# crankshaft_angle.net
KiCad netlist of a schematic drawn in EAGLE
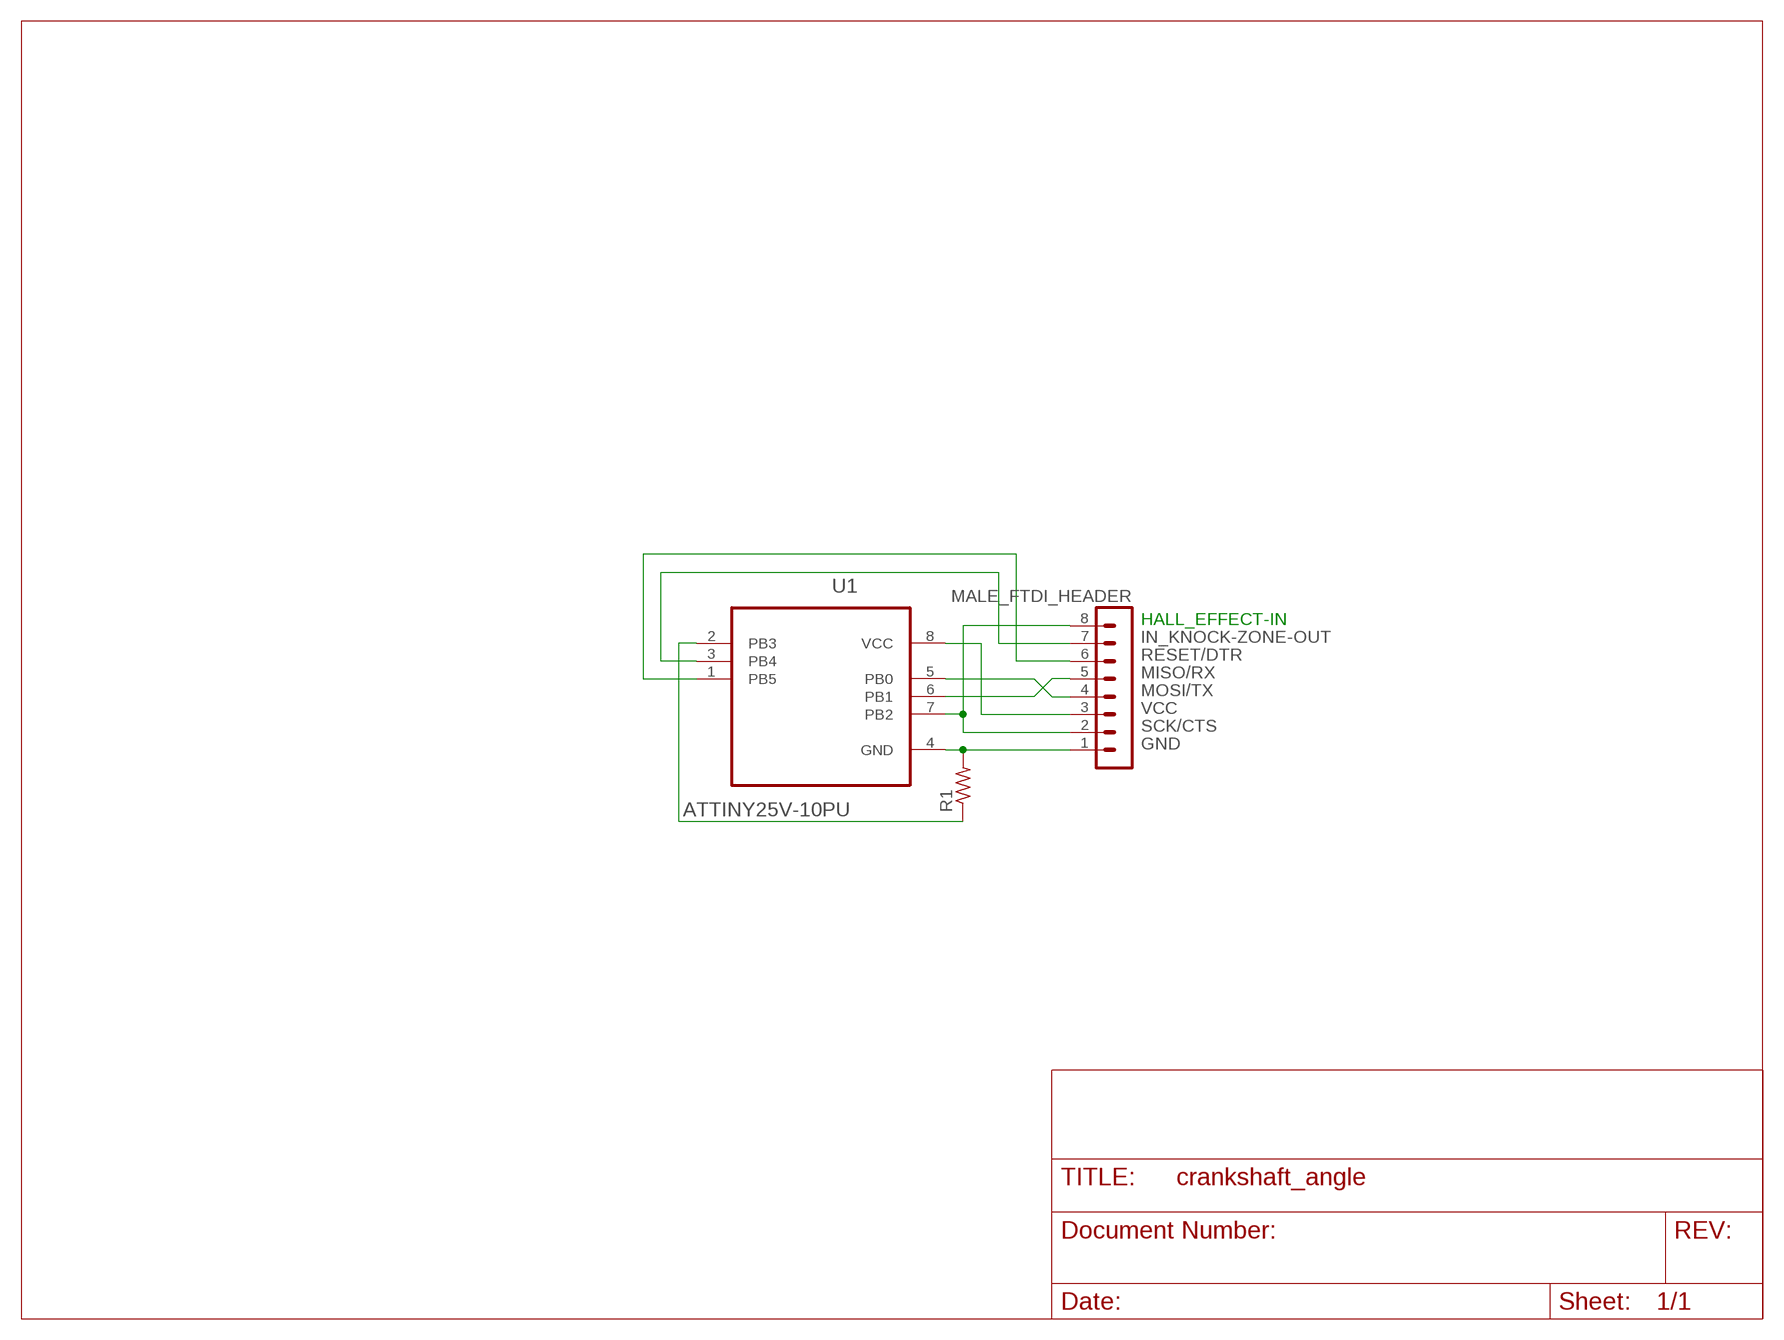
[diagram p0: schematic, sheet 1]

(export (version "E")
  (design (tool "Eeschema 10.0.6"))
  (components
    (comp (ref "MALE_FTDI_HEADER")
      (value "MA08-1")
      (footprint "eagle-import:MA08-1")
      (libsource (lib "eagle-import") (part "MA08-1"))
    )
    (comp (ref "R1")
      (value "R-US_0204/7")
      (footprint "eagle-import:0204_7")
      (libsource (lib "eagle-import") (part "R-US_0204/7"))
    )
    (comp (ref "U1")
      (value "ATTINY25V-10PU")
      (footprint "eagle-import:DIP254P762X533-8")
      (libsource (lib "eagle-import") (part "ATTINY25V-10PU"))
    )
  )
  (nets
    (net (code "1") (name "/GND") (class "Default")
      (node (ref "MALE_FTDI_HEADER") (pin "1") (pinfunction "1_1") (pintype "passive"))
      (node (ref "R1") (pin "2") (pinfunction "2_2") (pintype "passive"))
      (node (ref "U1") (pin "4") (pinfunction "GND_4") (pintype "passive"))
    )
    (net (code "2") (name "/IN_KNOCK-ZONE-OUT") (class "Default")
      (node (ref "MALE_FTDI_HEADER") (pin "7") (pinfunction "7_7") (pintype "passive"))
      (node (ref "U1") (pin "3") (pinfunction "PB4_3") (pintype "bidirectional"))
    )
    (net (code "3") (name "/MISO{slash}RX") (class "Default")
      (node (ref "MALE_FTDI_HEADER") (pin "5") (pinfunction "5_5") (pintype "passive"))
      (node (ref "U1") (pin "6") (pinfunction "PB1_6") (pintype "bidirectional"))
    )
    (net (code "4") (name "/MOSI{slash}TX") (class "Default")
      (node (ref "MALE_FTDI_HEADER") (pin "4") (pinfunction "4_4") (pintype "passive"))
      (node (ref "U1") (pin "5") (pinfunction "PB0_5") (pintype "bidirectional"))
    )
    (net (code "5") (name "/RESET{slash}DTR") (class "Default")
      (node (ref "MALE_FTDI_HEADER") (pin "6") (pinfunction "6_6") (pintype "passive"))
      (node (ref "U1") (pin "1") (pinfunction "PB5_1") (pintype "bidirectional"))
    )
    (net (code "6") (name "/SCK{slash}CTS") (class "Default")
      (node (ref "MALE_FTDI_HEADER") (pin "2") (pinfunction "2_2") (pintype "passive"))
      (node (ref "MALE_FTDI_HEADER") (pin "8") (pinfunction "8_8") (pintype "passive"))
      (node (ref "U1") (pin "7") (pinfunction "PB2_7") (pintype "bidirectional"))
    )
    (net (code "7") (name "/VCC") (class "Default")
      (node (ref "MALE_FTDI_HEADER") (pin "3") (pinfunction "3_3") (pintype "passive"))
      (node (ref "U1") (pin "8") (pinfunction "VCC_8") (pintype "power_in"))
    )
    (net (code "8") (name "Net-(U1-PB3)") (class "Default")
      (node (ref "R1") (pin "1") (pinfunction "1_1") (pintype "passive"))
      (node (ref "U1") (pin "2") (pinfunction "PB3_2") (pintype "bidirectional"))
    )
  )
)
